# ledmatrixv2.net
KiCad netlist of a schematic drawn in EAGLE
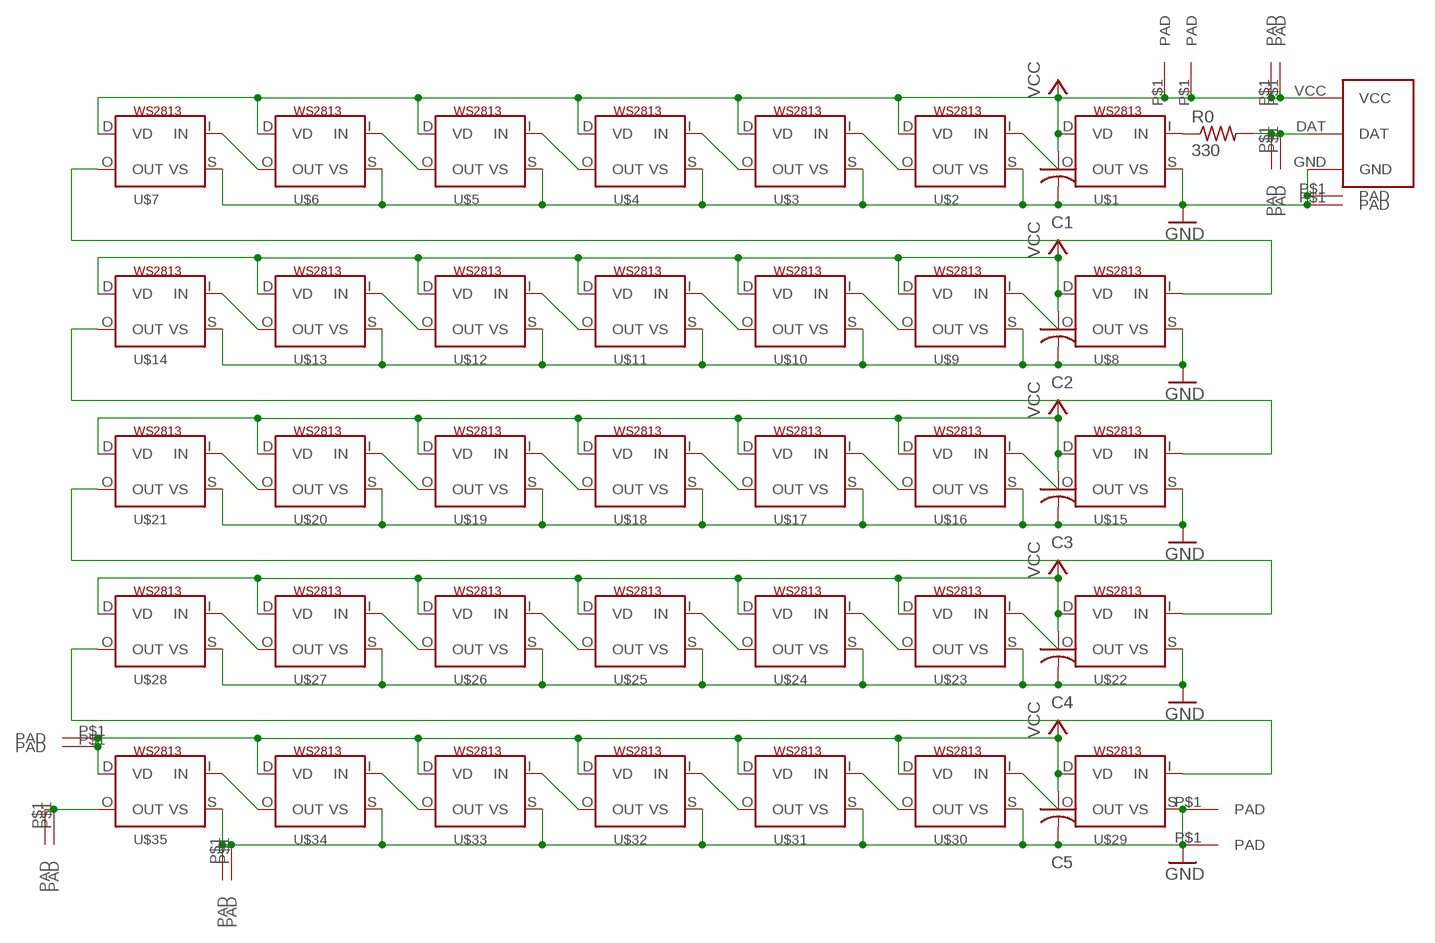
[diagram p0: schematic, sheet 1]

(export (version "E")
  (design (tool "Eeschema 10.0.6"))
  (components
    (comp (ref "C1")
      (value "C-USC0603K")
      (footprint "eagle-import:C0603K")
      (libsource (lib "eagle-import") (part "C-USC0603K"))
    )
    (comp (ref "C2")
      (value "C-USC0603K")
      (footprint "eagle-import:C0603K")
      (libsource (lib "eagle-import") (part "C-USC0603K"))
    )
    (comp (ref "C3")
      (value "C-USC0603K")
      (footprint "eagle-import:C0603K")
      (libsource (lib "eagle-import") (part "C-USC0603K"))
    )
    (comp (ref "C4")
      (value "C-USC0603K")
      (footprint "eagle-import:C0603K")
      (libsource (lib "eagle-import") (part "C-USC0603K"))
    )
    (comp (ref "C5")
      (value "C-USC0603K")
      (footprint "eagle-import:C0603K")
      (libsource (lib "eagle-import") (part "C-USC0603K"))
    )
    (comp (ref "R0")
      (value "330")
      (footprint "eagle-import:R0603")
      (libsource (lib "eagle-import") (part "R-US_R0603"))
    )
    (comp (ref "U$1")
      (value "WS2813")
      (footprint "eagle-import:RGBLED5050_4")
      (libsource (lib "eagle-import") (part "WS2813"))
    )
    (comp (ref "U$2")
      (value "WS2813")
      (footprint "eagle-import:RGBLED5050_4")
      (libsource (lib "eagle-import") (part "WS2813"))
    )
    (comp (ref "U$3")
      (value "WS2813")
      (footprint "eagle-import:RGBLED5050_4")
      (libsource (lib "eagle-import") (part "WS2813"))
    )
    (comp (ref "U$4")
      (value "WS2813")
      (footprint "eagle-import:RGBLED5050_4")
      (libsource (lib "eagle-import") (part "WS2813"))
    )
    (comp (ref "U$5")
      (value "WS2813")
      (footprint "eagle-import:RGBLED5050_4")
      (libsource (lib "eagle-import") (part "WS2813"))
    )
    (comp (ref "U$6")
      (value "WS2813")
      (footprint "eagle-import:RGBLED5050_4")
      (libsource (lib "eagle-import") (part "WS2813"))
    )
    (comp (ref "U$7")
      (value "WS2813")
      (footprint "eagle-import:RGBLED5050_4")
      (libsource (lib "eagle-import") (part "WS2813"))
    )
    (comp (ref "U$8")
      (value "WS2813")
      (footprint "eagle-import:RGBLED5050_4")
      (libsource (lib "eagle-import") (part "WS2813"))
    )
    (comp (ref "U$9")
      (value "WS2813")
      (footprint "eagle-import:RGBLED5050_4")
      (libsource (lib "eagle-import") (part "WS2813"))
    )
    (comp (ref "U$10")
      (value "WS2813")
      (footprint "eagle-import:RGBLED5050_4")
      (libsource (lib "eagle-import") (part "WS2813"))
    )
    (comp (ref "U$11")
      (value "WS2813")
      (footprint "eagle-import:RGBLED5050_4")
      (libsource (lib "eagle-import") (part "WS2813"))
    )
    (comp (ref "U$12")
      (value "WS2813")
      (footprint "eagle-import:RGBLED5050_4")
      (libsource (lib "eagle-import") (part "WS2813"))
    )
    (comp (ref "U$13")
      (value "WS2813")
      (footprint "eagle-import:RGBLED5050_4")
      (libsource (lib "eagle-import") (part "WS2813"))
    )
    (comp (ref "U$14")
      (value "WS2813")
      (footprint "eagle-import:RGBLED5050_4")
      (libsource (lib "eagle-import") (part "WS2813"))
    )
    (comp (ref "U$15")
      (value "WS2813")
      (footprint "eagle-import:RGBLED5050_4")
      (libsource (lib "eagle-import") (part "WS2813"))
    )
    (comp (ref "U$16")
      (value "WS2813")
      (footprint "eagle-import:RGBLED5050_4")
      (libsource (lib "eagle-import") (part "WS2813"))
    )
    (comp (ref "U$17")
      (value "WS2813")
      (footprint "eagle-import:RGBLED5050_4")
      (libsource (lib "eagle-import") (part "WS2813"))
    )
    (comp (ref "U$18")
      (value "WS2813")
      (footprint "eagle-import:RGBLED5050_4")
      (libsource (lib "eagle-import") (part "WS2813"))
    )
    (comp (ref "U$19")
      (value "WS2813")
      (footprint "eagle-import:RGBLED5050_4")
      (libsource (lib "eagle-import") (part "WS2813"))
    )
    (comp (ref "U$20")
      (value "WS2813")
      (footprint "eagle-import:RGBLED5050_4")
      (libsource (lib "eagle-import") (part "WS2813"))
    )
    (comp (ref "U$21")
      (value "WS2813")
      (footprint "eagle-import:RGBLED5050_4")
      (libsource (lib "eagle-import") (part "WS2813"))
    )
    (comp (ref "U$22")
      (value "WS2813")
      (footprint "eagle-import:RGBLED5050_4")
      (libsource (lib "eagle-import") (part "WS2813"))
    )
    (comp (ref "U$23")
      (value "WS2813")
      (footprint "eagle-import:RGBLED5050_4")
      (libsource (lib "eagle-import") (part "WS2813"))
    )
    (comp (ref "U$24")
      (value "WS2813")
      (footprint "eagle-import:RGBLED5050_4")
      (libsource (lib "eagle-import") (part "WS2813"))
    )
    (comp (ref "U$25")
      (value "WS2813")
      (footprint "eagle-import:RGBLED5050_4")
      (libsource (lib "eagle-import") (part "WS2813"))
    )
    (comp (ref "U$26")
      (value "WS2813")
      (footprint "eagle-import:RGBLED5050_4")
      (libsource (lib "eagle-import") (part "WS2813"))
    )
    (comp (ref "U$27")
      (value "WS2813")
      (footprint "eagle-import:RGBLED5050_4")
      (libsource (lib "eagle-import") (part "WS2813"))
    )
    (comp (ref "U$28")
      (value "WS2813")
      (footprint "eagle-import:RGBLED5050_4")
      (libsource (lib "eagle-import") (part "WS2813"))
    )
    (comp (ref "U$29")
      (value "WS2813")
      (footprint "eagle-import:RGBLED5050_4")
      (libsource (lib "eagle-import") (part "WS2813"))
    )
    (comp (ref "U$30")
      (value "WS2813")
      (footprint "eagle-import:RGBLED5050_4")
      (libsource (lib "eagle-import") (part "WS2813"))
    )
    (comp (ref "U$31")
      (value "WS2813")
      (footprint "eagle-import:RGBLED5050_4")
      (libsource (lib "eagle-import") (part "WS2813"))
    )
    (comp (ref "U$32")
      (value "WS2813")
      (footprint "eagle-import:RGBLED5050_4")
      (libsource (lib "eagle-import") (part "WS2813"))
    )
    (comp (ref "U$33")
      (value "WS2813")
      (footprint "eagle-import:RGBLED5050_4")
      (libsource (lib "eagle-import") (part "WS2813"))
    )
    (comp (ref "U$34")
      (value "WS2813")
      (footprint "eagle-import:RGBLED5050_4")
      (libsource (lib "eagle-import") (part "WS2813"))
    )
    (comp (ref "U$35")
      (value "WS2813")
      (footprint "eagle-import:RGBLED5050_4")
      (libsource (lib "eagle-import") (part "WS2813"))
    )
    (comp (ref "U$36")
      (value "SQWMINI-MATRIX")
      (footprint "eagle-import:SQWMINI-MATRIX")
      (libsource (lib "eagle-import") (part "SQWMINI-MATRIX"))
    )
    (comp (ref "U$37")
      (value "TESTPAD")
      (footprint "eagle-import:TESTPAD")
      (libsource (lib "eagle-import") (part "TESTPAD"))
    )
    (comp (ref "U$38")
      (value "TESTPAD")
      (footprint "eagle-import:TESTPAD")
      (libsource (lib "eagle-import") (part "TESTPAD"))
    )
    (comp (ref "U$39")
      (value "TESTPAD")
      (footprint "eagle-import:TESTPAD")
      (libsource (lib "eagle-import") (part "TESTPAD"))
    )
    (comp (ref "U$40")
      (value "TESTPAD")
      (footprint "eagle-import:TESTPAD")
      (libsource (lib "eagle-import") (part "TESTPAD"))
    )
    (comp (ref "U$41")
      (value "TESTPAD")
      (footprint "eagle-import:TESTPAD")
      (libsource (lib "eagle-import") (part "TESTPAD"))
    )
    (comp (ref "U$42")
      (value "TESTPAD")
      (footprint "eagle-import:TESTPAD")
      (libsource (lib "eagle-import") (part "TESTPAD"))
    )
    (comp (ref "U$43")
      (value "TESTPAD")
      (footprint "eagle-import:TESTPAD")
      (libsource (lib "eagle-import") (part "TESTPAD"))
    )
    (comp (ref "U$44")
      (value "TESTPAD")
      (footprint "eagle-import:TESTPAD")
      (libsource (lib "eagle-import") (part "TESTPAD"))
    )
    (comp (ref "U$45")
      (value "TESTPAD")
      (footprint "eagle-import:TESTPAD")
      (libsource (lib "eagle-import") (part "TESTPAD"))
    )
    (comp (ref "U$46")
      (value "TESTPAD")
      (footprint "eagle-import:TESTPAD")
      (libsource (lib "eagle-import") (part "TESTPAD"))
    )
    (comp (ref "U$47")
      (value "TESTPAD")
      (footprint "eagle-import:TESTPAD")
      (libsource (lib "eagle-import") (part "TESTPAD"))
    )
    (comp (ref "U$48")
      (value "TESTPAD")
      (footprint "eagle-import:TESTPAD")
      (libsource (lib "eagle-import") (part "TESTPAD"))
    )
    (comp (ref "U$49")
      (value "TESTPAD")
      (footprint "eagle-import:TESTPAD")
      (libsource (lib "eagle-import") (part "TESTPAD"))
    )
    (comp (ref "U$50")
      (value "TESTPAD")
      (footprint "eagle-import:TESTPAD")
      (libsource (lib "eagle-import") (part "TESTPAD"))
    )
    (comp (ref "U$51")
      (value "TESTPAD")
      (footprint "eagle-import:TESTPAD")
      (libsource (lib "eagle-import") (part "TESTPAD"))
    )
    (comp (ref "U$52")
      (value "TESTPAD")
      (footprint "eagle-import:TESTPAD")
      (libsource (lib "eagle-import") (part "TESTPAD"))
    )
  )
  (nets
    (net (code "1") (name "GND") (class "Default")
      (node (ref "C1") (pin "2") (pinfunction "2_2") (pintype "passive"))
      (node (ref "C2") (pin "2") (pinfunction "2_2") (pintype "passive"))
      (node (ref "C3") (pin "2") (pinfunction "2_2") (pintype "passive"))
      (node (ref "C4") (pin "2") (pinfunction "2_2") (pintype "passive"))
      (node (ref "C5") (pin "2") (pinfunction "2_2") (pintype "passive"))
      (node (ref "U$1") (pin "S") (pinfunction "VS_S") (pintype "power_in"))
      (node (ref "U$10") (pin "S") (pinfunction "VS_S") (pintype "power_in"))
      (node (ref "U$11") (pin "S") (pinfunction "VS_S") (pintype "power_in"))
      (node (ref "U$12") (pin "S") (pinfunction "VS_S") (pintype "power_in"))
      (node (ref "U$13") (pin "S") (pinfunction "VS_S") (pintype "power_in"))
      (node (ref "U$14") (pin "S") (pinfunction "VS_S") (pintype "power_in"))
      (node (ref "U$15") (pin "S") (pinfunction "VS_S") (pintype "power_in"))
      (node (ref "U$16") (pin "S") (pinfunction "VS_S") (pintype "power_in"))
      (node (ref "U$17") (pin "S") (pinfunction "VS_S") (pintype "power_in"))
      (node (ref "U$18") (pin "S") (pinfunction "VS_S") (pintype "power_in"))
      (node (ref "U$19") (pin "S") (pinfunction "VS_S") (pintype "power_in"))
      (node (ref "U$2") (pin "S") (pinfunction "VS_S") (pintype "power_in"))
      (node (ref "U$20") (pin "S") (pinfunction "VS_S") (pintype "power_in"))
      (node (ref "U$21") (pin "S") (pinfunction "VS_S") (pintype "power_in"))
      (node (ref "U$22") (pin "S") (pinfunction "VS_S") (pintype "power_in"))
      (node (ref "U$23") (pin "S") (pinfunction "VS_S") (pintype "power_in"))
      (node (ref "U$24") (pin "S") (pinfunction "VS_S") (pintype "power_in"))
      (node (ref "U$25") (pin "S") (pinfunction "VS_S") (pintype "power_in"))
      (node (ref "U$26") (pin "S") (pinfunction "VS_S") (pintype "power_in"))
      (node (ref "U$27") (pin "S") (pinfunction "VS_S") (pintype "power_in"))
      (node (ref "U$28") (pin "S") (pinfunction "VS_S") (pintype "power_in"))
      (node (ref "U$29") (pin "S") (pinfunction "VS_S") (pintype "power_in"))
      (node (ref "U$3") (pin "S") (pinfunction "VS_S") (pintype "power_in"))
      (node (ref "U$30") (pin "S") (pinfunction "VS_S") (pintype "power_in"))
      (node (ref "U$31") (pin "S") (pinfunction "VS_S") (pintype "power_in"))
      (node (ref "U$32") (pin "S") (pinfunction "VS_S") (pintype "power_in"))
      (node (ref "U$33") (pin "S") (pinfunction "VS_S") (pintype "power_in"))
      (node (ref "U$34") (pin "S") (pinfunction "VS_S") (pintype "power_in"))
      (node (ref "U$35") (pin "S") (pinfunction "VS_S") (pintype "power_in"))
      (node (ref "U$36") (pin "GND") (pinfunction "GND_GND") (pintype "bidirectional"))
      (node (ref "U$39") (pin "P$1") (pinfunction "PAD_P$1") (pintype "bidirectional"))
      (node (ref "U$4") (pin "S") (pinfunction "VS_S") (pintype "power_in"))
      (node (ref "U$40") (pin "P$1") (pinfunction "PAD_P$1") (pintype "bidirectional"))
      (node (ref "U$45") (pin "P$1") (pinfunction "PAD_P$1") (pintype "bidirectional"))
      (node (ref "U$46") (pin "P$1") (pinfunction "PAD_P$1") (pintype "bidirectional"))
      (node (ref "U$5") (pin "S") (pinfunction "VS_S") (pintype "power_in"))
      (node (ref "U$50") (pin "P$1") (pinfunction "PAD_P$1") (pintype "bidirectional"))
      (node (ref "U$52") (pin "P$1") (pinfunction "PAD_P$1") (pintype "bidirectional"))
      (node (ref "U$6") (pin "S") (pinfunction "VS_S") (pintype "power_in"))
      (node (ref "U$7") (pin "S") (pinfunction "VS_S") (pintype "power_in"))
      (node (ref "U$8") (pin "S") (pinfunction "VS_S") (pintype "power_in"))
      (node (ref "U$9") (pin "S") (pinfunction "VS_S") (pintype "power_in"))
    )
    (net (code "2") (name "Net-(U$1-IN)") (class "Default")
      (node (ref "R0") (pin "1") (pinfunction "1_1") (pintype "passive"))
      (node (ref "U$1") (pin "I") (pinfunction "IN_I") (pintype "input"))
    )
    (net (code "3") (name "Net-(U$1-OUT)") (class "Default")
      (node (ref "U$1") (pin "O") (pinfunction "OUT_O") (pintype "output"))
      (node (ref "U$2") (pin "I") (pinfunction "IN_I") (pintype "input"))
    )
    (net (code "4") (name "Net-(U$2-OUT)") (class "Default")
      (node (ref "U$2") (pin "O") (pinfunction "OUT_O") (pintype "output"))
      (node (ref "U$3") (pin "I") (pinfunction "IN_I") (pintype "input"))
    )
    (net (code "5") (name "Net-(U$3-OUT)") (class "Default")
      (node (ref "U$3") (pin "O") (pinfunction "OUT_O") (pintype "output"))
      (node (ref "U$4") (pin "I") (pinfunction "IN_I") (pintype "input"))
    )
    (net (code "6") (name "Net-(U$4-OUT)") (class "Default")
      (node (ref "U$4") (pin "O") (pinfunction "OUT_O") (pintype "output"))
      (node (ref "U$5") (pin "I") (pinfunction "IN_I") (pintype "input"))
    )
    (net (code "7") (name "Net-(U$5-OUT)") (class "Default")
      (node (ref "U$5") (pin "O") (pinfunction "OUT_O") (pintype "output"))
      (node (ref "U$6") (pin "I") (pinfunction "IN_I") (pintype "input"))
    )
    (net (code "8") (name "Net-(U$6-OUT)") (class "Default")
      (node (ref "U$6") (pin "O") (pinfunction "OUT_O") (pintype "output"))
      (node (ref "U$7") (pin "I") (pinfunction "IN_I") (pintype "input"))
    )
    (net (code "9") (name "Net-(U$7-OUT)") (class "Default")
      (node (ref "U$7") (pin "O") (pinfunction "OUT_O") (pintype "output"))
      (node (ref "U$8") (pin "I") (pinfunction "IN_I") (pintype "input"))
    )
    (net (code "10") (name "Net-(U$8-OUT)") (class "Default")
      (node (ref "U$8") (pin "O") (pinfunction "OUT_O") (pintype "output"))
      (node (ref "U$9") (pin "I") (pinfunction "IN_I") (pintype "input"))
    )
    (net (code "11") (name "Net-(U$10-IN)") (class "Default")
      (node (ref "U$10") (pin "I") (pinfunction "IN_I") (pintype "input"))
      (node (ref "U$9") (pin "O") (pinfunction "OUT_O") (pintype "output"))
    )
    (net (code "12") (name "Net-(U$10-OUT)") (class "Default")
      (node (ref "U$10") (pin "O") (pinfunction "OUT_O") (pintype "output"))
      (node (ref "U$11") (pin "I") (pinfunction "IN_I") (pintype "input"))
    )
    (net (code "13") (name "Net-(U$11-OUT)") (class "Default")
      (node (ref "U$11") (pin "O") (pinfunction "OUT_O") (pintype "output"))
      (node (ref "U$12") (pin "I") (pinfunction "IN_I") (pintype "input"))
    )
    (net (code "14") (name "Net-(U$12-OUT)") (class "Default")
      (node (ref "U$12") (pin "O") (pinfunction "OUT_O") (pintype "output"))
      (node (ref "U$13") (pin "I") (pinfunction "IN_I") (pintype "input"))
    )
    (net (code "15") (name "Net-(U$13-OUT)") (class "Default")
      (node (ref "U$13") (pin "O") (pinfunction "OUT_O") (pintype "output"))
      (node (ref "U$14") (pin "I") (pinfunction "IN_I") (pintype "input"))
    )
    (net (code "16") (name "Net-(U$14-OUT)") (class "Default")
      (node (ref "U$14") (pin "O") (pinfunction "OUT_O") (pintype "output"))
      (node (ref "U$15") (pin "I") (pinfunction "IN_I") (pintype "input"))
    )
    (net (code "17") (name "Net-(U$15-OUT)") (class "Default")
      (node (ref "U$15") (pin "O") (pinfunction "OUT_O") (pintype "output"))
      (node (ref "U$16") (pin "I") (pinfunction "IN_I") (pintype "input"))
    )
    (net (code "18") (name "Net-(U$16-OUT)") (class "Default")
      (node (ref "U$16") (pin "O") (pinfunction "OUT_O") (pintype "output"))
      (node (ref "U$17") (pin "I") (pinfunction "IN_I") (pintype "input"))
    )
    (net (code "19") (name "Net-(U$17-OUT)") (class "Default")
      (node (ref "U$17") (pin "O") (pinfunction "OUT_O") (pintype "output"))
      (node (ref "U$18") (pin "I") (pinfunction "IN_I") (pintype "input"))
    )
    (net (code "20") (name "Net-(U$18-OUT)") (class "Default")
      (node (ref "U$18") (pin "O") (pinfunction "OUT_O") (pintype "output"))
      (node (ref "U$19") (pin "I") (pinfunction "IN_I") (pintype "input"))
    )
    (net (code "21") (name "Net-(U$19-OUT)") (class "Default")
      (node (ref "U$19") (pin "O") (pinfunction "OUT_O") (pintype "output"))
      (node (ref "U$20") (pin "I") (pinfunction "IN_I") (pintype "input"))
    )
    (net (code "22") (name "Net-(U$20-OUT)") (class "Default")
      (node (ref "U$20") (pin "O") (pinfunction "OUT_O") (pintype "output"))
      (node (ref "U$21") (pin "I") (pinfunction "IN_I") (pintype "input"))
    )
    (net (code "23") (name "Net-(U$21-OUT)") (class "Default")
      (node (ref "U$21") (pin "O") (pinfunction "OUT_O") (pintype "output"))
      (node (ref "U$22") (pin "I") (pinfunction "IN_I") (pintype "input"))
    )
    (net (code "24") (name "Net-(U$22-OUT)") (class "Default")
      (node (ref "U$22") (pin "O") (pinfunction "OUT_O") (pintype "output"))
      (node (ref "U$23") (pin "I") (pinfunction "IN_I") (pintype "input"))
    )
    (net (code "25") (name "Net-(U$23-OUT)") (class "Default")
      (node (ref "U$23") (pin "O") (pinfunction "OUT_O") (pintype "output"))
      (node (ref "U$24") (pin "I") (pinfunction "IN_I") (pintype "input"))
    )
    (net (code "26") (name "Net-(U$24-OUT)") (class "Default")
      (node (ref "U$24") (pin "O") (pinfunction "OUT_O") (pintype "output"))
      (node (ref "U$25") (pin "I") (pinfunction "IN_I") (pintype "input"))
    )
    (net (code "27") (name "Net-(U$25-OUT)") (class "Default")
      (node (ref "U$25") (pin "O") (pinfunction "OUT_O") (pintype "output"))
      (node (ref "U$26") (pin "I") (pinfunction "IN_I") (pintype "input"))
    )
    (net (code "28") (name "Net-(U$26-OUT)") (class "Default")
      (node (ref "U$26") (pin "O") (pinfunction "OUT_O") (pintype "output"))
      (node (ref "U$27") (pin "I") (pinfunction "IN_I") (pintype "input"))
    )
    (net (code "29") (name "Net-(U$27-OUT)") (class "Default")
      (node (ref "U$27") (pin "O") (pinfunction "OUT_O") (pintype "output"))
      (node (ref "U$28") (pin "I") (pinfunction "IN_I") (pintype "input"))
    )
    (net (code "30") (name "Net-(U$28-OUT)") (class "Default")
      (node (ref "U$28") (pin "O") (pinfunction "OUT_O") (pintype "output"))
      (node (ref "U$29") (pin "I") (pinfunction "IN_I") (pintype "input"))
    )
    (net (code "31") (name "Net-(U$29-OUT)") (class "Default")
      (node (ref "U$29") (pin "O") (pinfunction "OUT_O") (pintype "output"))
      (node (ref "U$30") (pin "I") (pinfunction "IN_I") (pintype "input"))
    )
    (net (code "32") (name "Net-(U$30-OUT)") (class "Default")
      (node (ref "U$30") (pin "O") (pinfunction "OUT_O") (pintype "output"))
      (node (ref "U$31") (pin "I") (pinfunction "IN_I") (pintype "input"))
    )
    (net (code "33") (name "Net-(U$31-OUT)") (class "Default")
      (node (ref "U$31") (pin "O") (pinfunction "OUT_O") (pintype "output"))
      (node (ref "U$32") (pin "I") (pinfunction "IN_I") (pintype "input"))
    )
    (net (code "34") (name "Net-(U$32-OUT)") (class "Default")
      (node (ref "U$32") (pin "O") (pinfunction "OUT_O") (pintype "output"))
      (node (ref "U$33") (pin "I") (pinfunction "IN_I") (pintype "input"))
    )
    (net (code "35") (name "Net-(U$33-OUT)") (class "Default")
      (node (ref "U$33") (pin "O") (pinfunction "OUT_O") (pintype "output"))
      (node (ref "U$34") (pin "I") (pinfunction "IN_I") (pintype "input"))
    )
    (net (code "36") (name "Net-(U$34-OUT)") (class "Default")
      (node (ref "U$34") (pin "O") (pinfunction "OUT_O") (pintype "output"))
      (node (ref "U$35") (pin "I") (pinfunction "IN_I") (pintype "input"))
    )
    (net (code "37") (name "Net-(U$35-OUT)") (class "Default")
      (node (ref "U$35") (pin "O") (pinfunction "OUT_O") (pintype "output"))
      (node (ref "U$47") (pin "P$1") (pinfunction "PAD_P$1") (pintype "bidirectional"))
      (node (ref "U$48") (pin "P$1") (pinfunction "PAD_P$1") (pintype "bidirectional"))
    )
    (net (code "38") (name "Net-(U$41-PAD)") (class "Default")
      (node (ref "R0") (pin "2") (pinfunction "2_2") (pintype "passive"))
      (node (ref "U$36") (pin "DAT") (pinfunction "DAT_DAT") (pintype "bidirectional"))
      (node (ref "U$41") (pin "P$1") (pinfunction "PAD_P$1") (pintype "bidirectional"))
      (node (ref "U$42") (pin "P$1") (pinfunction "PAD_P$1") (pintype "bidirectional"))
    )
    (net (code "39") (name "VCC") (class "Default")
      (node (ref "C1") (pin "1") (pinfunction "1_1") (pintype "passive"))
      (node (ref "C2") (pin "1") (pinfunction "1_1") (pintype "passive"))
      (node (ref "C3") (pin "1") (pinfunction "1_1") (pintype "passive"))
      (node (ref "C4") (pin "1") (pinfunction "1_1") (pintype "passive"))
      (node (ref "C5") (pin "1") (pinfunction "1_1") (pintype "passive"))
      (node (ref "U$1") (pin "D") (pinfunction "VD_D") (pintype "power_in"))
      (node (ref "U$10") (pin "D") (pinfunction "VD_D") (pintype "power_in"))
      (node (ref "U$11") (pin "D") (pinfunction "VD_D") (pintype "power_in"))
      (node (ref "U$12") (pin "D") (pinfunction "VD_D") (pintype "power_in"))
      (node (ref "U$13") (pin "D") (pinfunction "VD_D") (pintype "power_in"))
      (node (ref "U$14") (pin "D") (pinfunction "VD_D") (pintype "power_in"))
      (node (ref "U$15") (pin "D") (pinfunction "VD_D") (pintype "power_in"))
      (node (ref "U$16") (pin "D") (pinfunction "VD_D") (pintype "power_in"))
      (node (ref "U$17") (pin "D") (pinfunction "VD_D") (pintype "power_in"))
      (node (ref "U$18") (pin "D") (pinfunction "VD_D") (pintype "power_in"))
      (node (ref "U$19") (pin "D") (pinfunction "VD_D") (pintype "power_in"))
      (node (ref "U$2") (pin "D") (pinfunction "VD_D") (pintype "power_in"))
      (node (ref "U$20") (pin "D") (pinfunction "VD_D") (pintype "power_in"))
      (node (ref "U$21") (pin "D") (pinfunction "VD_D") (pintype "power_in"))
      (node (ref "U$22") (pin "D") (pinfunction "VD_D") (pintype "power_in"))
      (node (ref "U$23") (pin "D") (pinfunction "VD_D") (pintype "power_in"))
      (node (ref "U$24") (pin "D") (pinfunction "VD_D") (pintype "power_in"))
      (node (ref "U$25") (pin "D") (pinfunction "VD_D") (pintype "power_in"))
      (node (ref "U$26") (pin "D") (pinfunction "VD_D") (pintype "power_in"))
      (node (ref "U$27") (pin "D") (pinfunction "VD_D") (pintype "power_in"))
      (node (ref "U$28") (pin "D") (pinfunction "VD_D") (pintype "power_in"))
      (node (ref "U$29") (pin "D") (pinfunction "VD_D") (pintype "power_in"))
      (node (ref "U$3") (pin "D") (pinfunction "VD_D") (pintype "power_in"))
      (node (ref "U$30") (pin "D") (pinfunction "VD_D") (pintype "power_in"))
      (node (ref "U$31") (pin "D") (pinfunction "VD_D") (pintype "power_in"))
      (node (ref "U$32") (pin "D") (pinfunction "VD_D") (pintype "power_in"))
      (node (ref "U$33") (pin "D") (pinfunction "VD_D") (pintype "power_in"))
      (node (ref "U$34") (pin "D") (pinfunction "VD_D") (pintype "power_in"))
      (node (ref "U$35") (pin "D") (pinfunction "VD_D") (pintype "power_in"))
      (node (ref "U$36") (pin "VCC") (pinfunction "VCC_VCC") (pintype "bidirectional"))
      (node (ref "U$37") (pin "P$1") (pinfunction "PAD_P$1") (pintype "bidirectional"))
      (node (ref "U$38") (pin "P$1") (pinfunction "PAD_P$1") (pintype "bidirectional"))
      (node (ref "U$4") (pin "D") (pinfunction "VD_D") (pintype "power_in"))
      (node (ref "U$43") (pin "P$1") (pinfunction "PAD_P$1") (pintype "bidirectional"))
      (node (ref "U$44") (pin "P$1") (pinfunction "PAD_P$1") (pintype "bidirectional"))
      (node (ref "U$49") (pin "P$1") (pinfunction "PAD_P$1") (pintype "bidirectional"))
      (node (ref "U$5") (pin "D") (pinfunction "VD_D") (pintype "power_in"))
      (node (ref "U$51") (pin "P$1") (pinfunction "PAD_P$1") (pintype "bidirectional"))
      (node (ref "U$6") (pin "D") (pinfunction "VD_D") (pintype "power_in"))
      (node (ref "U$7") (pin "D") (pinfunction "VD_D") (pintype "power_in"))
      (node (ref "U$8") (pin "D") (pinfunction "VD_D") (pintype "power_in"))
      (node (ref "U$9") (pin "D") (pinfunction "VD_D") (pintype "power_in"))
    )
  )
)
